# HDC1010_Acorn.net
KiCad netlist of a schematic drawn in EAGLE
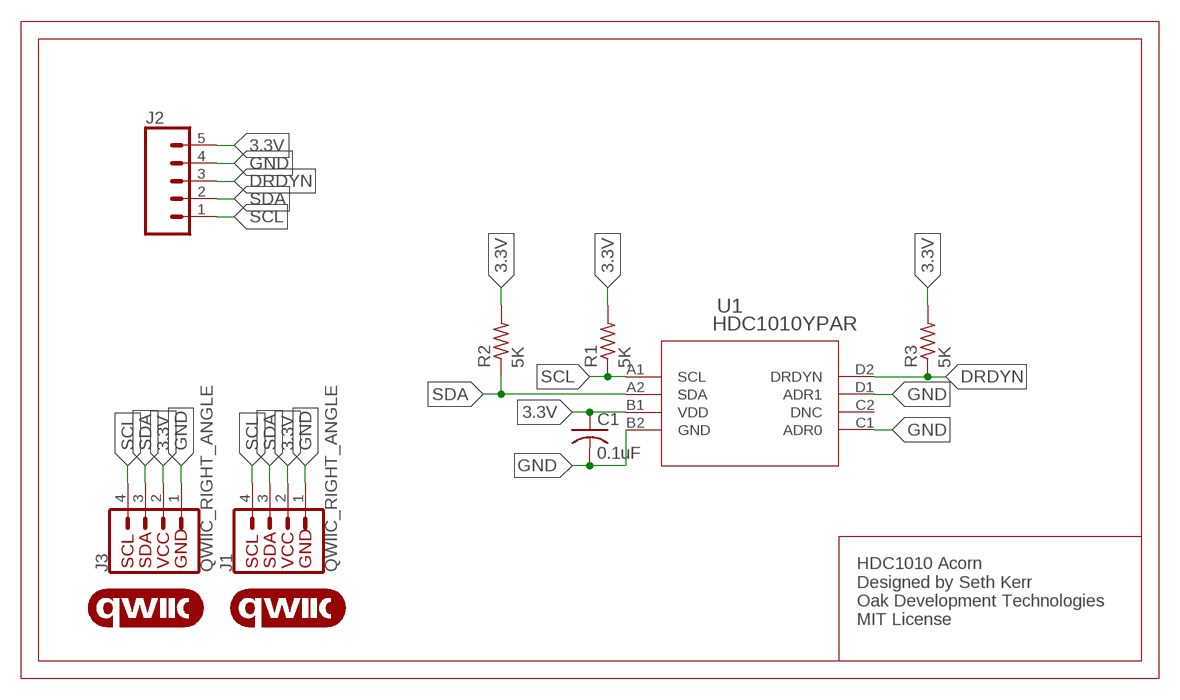
[diagram p0: schematic, sheet 1]

(export (version "E")
  (design (tool "Eeschema 10.0.6"))
  (components
    (comp (ref "C1")
      (value "0.1uF")
      (footprint "eagle-import:C0402")
      (libsource (lib "eagle-import") (part "C-USC0402"))
    )
    (comp (ref "J1")
      (value "QWIIC_RIGHT_ANGLE")
      (footprint "eagle-import:JST04_1MM_RA")
      (libsource (lib "eagle-import") (part "QWIIC_CONNECTORJS-1MM"))
    )
    (comp (ref "J2")
      (value "CONN_05NO_SILK")
      (footprint "eagle-import:1X05_NO_SILK")
      (libsource (lib "eagle-import") (part "CONN_05NO_SILK"))
    )
    (comp (ref "J3")
      (value "QWIIC_RIGHT_ANGLE")
      (footprint "eagle-import:JST04_1MM_RA")
      (libsource (lib "eagle-import") (part "QWIIC_CONNECTORJS-1MM"))
    )
    (comp (ref "LOGO1")
      (value "QWIIC_LOGO_3MM")
      (footprint "eagle-import:QWIIC_3MM")
      (libsource (lib "eagle-import") (part "QWIIC_LOGO_3MM"))
    )
    (comp (ref "LOGO2")
      (value "QWIIC_LOGO_3MM")
      (footprint "eagle-import:QWIIC_3MM")
      (libsource (lib "eagle-import") (part "QWIIC_LOGO_3MM"))
    )
    (comp (ref "R1")
      (value "5K")
      (footprint "eagle-import:R0603")
      (libsource (lib "eagle-import") (part "R-US_R0603"))
    )
    (comp (ref "R2")
      (value "5K")
      (footprint "eagle-import:R0603")
      (libsource (lib "eagle-import") (part "R-US_R0603"))
    )
    (comp (ref "R3")
      (value "5K")
      (footprint "eagle-import:R0603")
      (libsource (lib "eagle-import") (part "R-US_R0603"))
    )
    (comp (ref "U1")
      (value "HDC1010YPAR")
      (footprint "eagle-import:YPA8_TEX")
      (fields (field (name "COPYRIGHT") "Copyright (C) 2018 Accelerated Designs. All rights reserved"))
      (libsource (lib "eagle-import") (part "HDC1010YPAR"))
    )
  )
  (nets
    (net (code "1") (name "3.3V") (class "Default")
      (node (ref "C1") (pin "1") (pinfunction "1_1") (pintype "passive"))
      (node (ref "J1") (pin "2") (pinfunction "2_2") (pintype "power_in"))
      (node (ref "J2") (pin "5") (pinfunction "5_5") (pintype "passive"))
      (node (ref "J3") (pin "2") (pinfunction "2_2") (pintype "power_in"))
      (node (ref "R1") (pin "2") (pinfunction "2_2") (pintype "passive"))
      (node (ref "R2") (pin "2") (pinfunction "2_2") (pintype "passive"))
      (node (ref "R3") (pin "2") (pinfunction "2_2") (pintype "passive"))
      (node (ref "U1") (pin "B1") (pinfunction "VDD_B1") (pintype "power_in"))
    )
    (net (code "2") (name "DRDYN") (class "Default")
      (node (ref "J2") (pin "3") (pinfunction "3_3") (pintype "passive"))
      (node (ref "R3") (pin "1") (pinfunction "1_1") (pintype "passive"))
      (node (ref "U1") (pin "D2") (pinfunction "DRDYN_D2") (pintype "output"))
    )
    (net (code "3") (name "GND") (class "Default")
      (node (ref "C1") (pin "2") (pinfunction "2_2") (pintype "passive"))
      (node (ref "J1") (pin "1") (pinfunction "1_1") (pintype "power_in"))
      (node (ref "J2") (pin "4") (pinfunction "4_4") (pintype "passive"))
      (node (ref "J3") (pin "1") (pinfunction "1_1") (pintype "power_in"))
      (node (ref "U1") (pin "B2") (pinfunction "GND_B2") (pintype "power_in"))
      (node (ref "U1") (pin "C1") (pinfunction "ADR0_C1") (pintype "input"))
      (node (ref "U1") (pin "D1") (pinfunction "ADR1_D1") (pintype "input"))
    )
    (net (code "4") (name "SCL") (class "Default")
      (node (ref "J1") (pin "4") (pinfunction "4_4") (pintype "passive"))
      (node (ref "J2") (pin "1") (pinfunction "1_1") (pintype "passive"))
      (node (ref "J3") (pin "4") (pinfunction "4_4") (pintype "passive"))
      (node (ref "R1") (pin "1") (pinfunction "1_1") (pintype "passive"))
      (node (ref "U1") (pin "A1") (pinfunction "SCL_A1") (pintype "input"))
    )
    (net (code "5") (name "SDA") (class "Default")
      (node (ref "J1") (pin "3") (pinfunction "3_3") (pintype "passive"))
      (node (ref "J2") (pin "2") (pinfunction "2_2") (pintype "passive"))
      (node (ref "J3") (pin "3") (pinfunction "3_3") (pintype "passive"))
      (node (ref "R2") (pin "1") (pinfunction "1_1") (pintype "passive"))
      (node (ref "U1") (pin "A2") (pinfunction "SDA_A2") (pintype "bidirectional"))
    )
    (net (code "6") (name "unconnected-(U1-DNC-PadC2)") (class "Default")
      (node (ref "U1") (pin "C2") (pinfunction "DNC_C2") (pintype "no_connect"))
    )
  )
)
